# InterfacePagamentos.net
KiCad netlist of a schematic drawn in Altium Designer
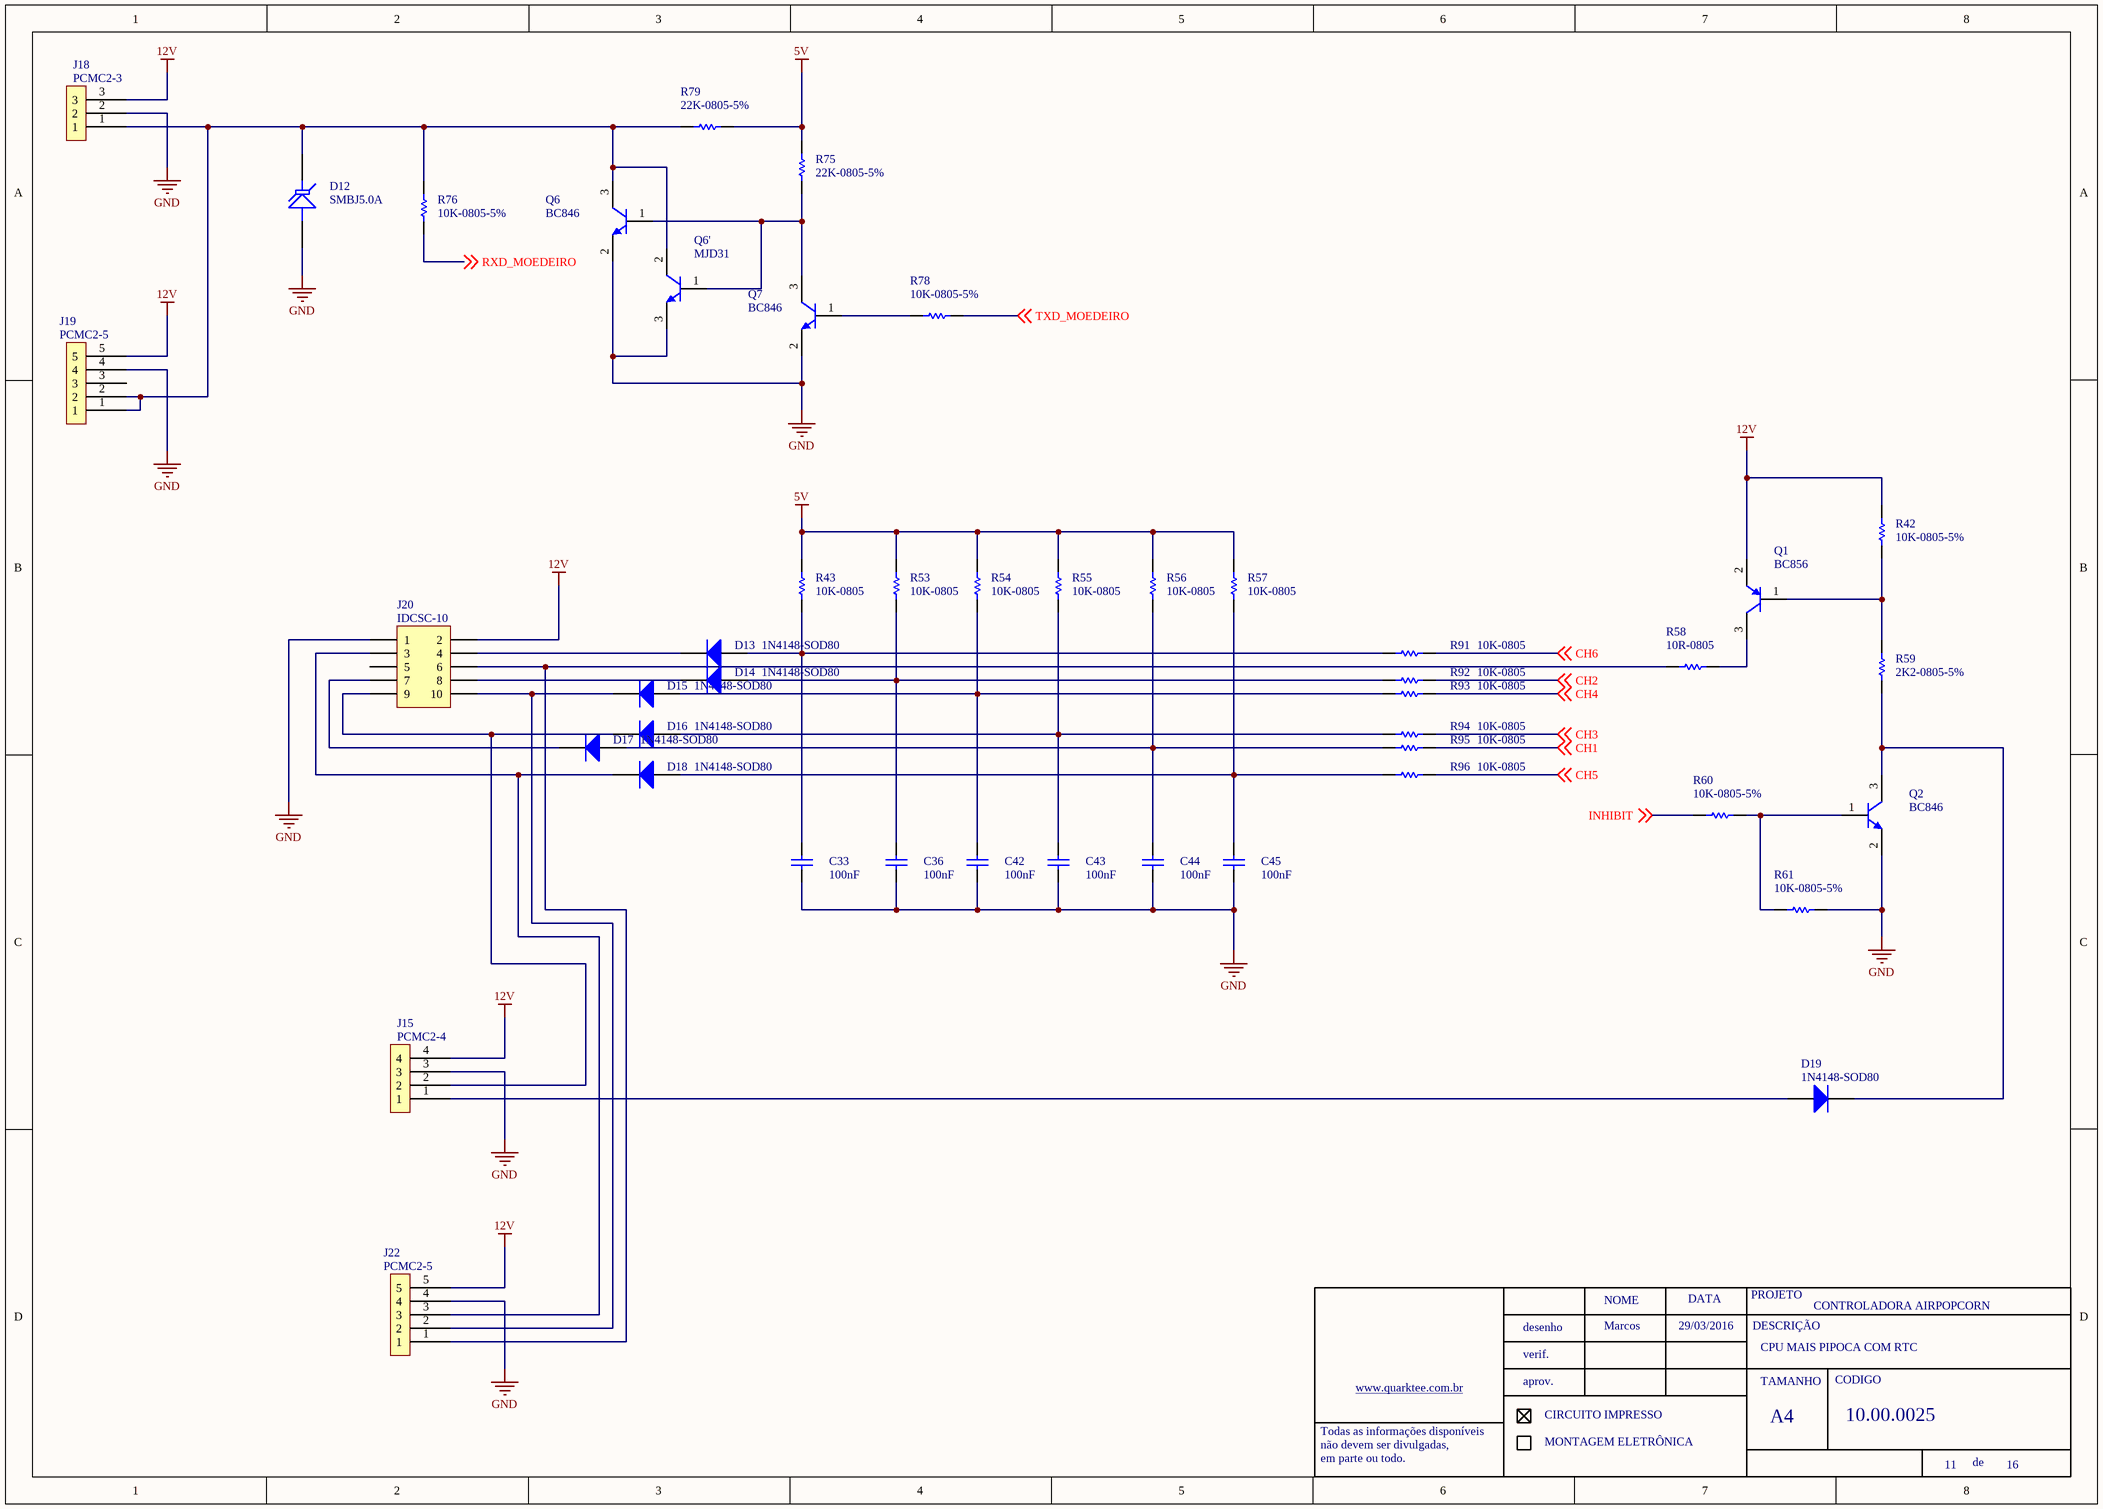
[diagram p0: InterfacePagamentos.SchDoc]

(export (version "E")
  (design (tool "Eeschema 10.0.6"))
  (components
    (comp (ref "C33")
      (value "100nF")
      (footprint "0805-REVISADO O")
      (description "100nF/50-0805-NPO")
      (libsource (lib "AquinoLib") (part "100nF/50-0805-NPO"))
    )
    (comp (ref "C36")
      (value "100nF")
      (footprint "0805-REVISADO O")
      (description "100nF/50-0805-NPO")
      (libsource (lib "AquinoLib") (part "100nF/50-0805-NPO"))
    )
    (comp (ref "C42")
      (value "100nF")
      (footprint "0805-REVISADO O")
      (description "100nF/50-0805-NPO")
      (libsource (lib "AquinoLib") (part "100nF/50-0805-NPO"))
    )
    (comp (ref "C43")
      (value "100nF")
      (footprint "0805-REVISADO O")
      (description "100nF/50-0805-NPO")
      (libsource (lib "AquinoLib") (part "100nF/50-0805-NPO"))
    )
    (comp (ref "C44")
      (value "100nF")
      (footprint "0805-REVISADO O")
      (description "100nF/50-0805-NPO")
      (libsource (lib "AquinoLib") (part "100nF/50-0805-NPO"))
    )
    (comp (ref "C45")
      (value "100nF")
      (footprint "0805-REVISADO O")
      (description "100nF/50-0805-NPO")
      (libsource (lib "AquinoLib") (part "100nF/50-0805-NPO"))
    )
    (comp (ref "D12")
      (value "SMBJ5.0A")
      (footprint "SMB/DO-214AA")
      (libsource (lib "AquinoLib") (part "SMBJ5.0A"))
    )
    (comp (ref "D13")
      (value "1N4148-SOD80")
      (footprint "MINIMLEF/SOD80")
      (libsource (lib "AquinoLib") (part "1N4148-SOD80"))
    )
    (comp (ref "D14")
      (value "1N4148-SOD80")
      (footprint "MINIMLEF/SOD80")
      (libsource (lib "AquinoLib") (part "1N4148-SOD80"))
    )
    (comp (ref "D15")
      (value "1N4148-SOD80")
      (footprint "MINIMLEF/SOD80")
      (libsource (lib "AquinoLib") (part "1N4148-SOD80"))
    )
    (comp (ref "D16")
      (value "1N4148-SOD80")
      (footprint "MINIMLEF/SOD80")
      (libsource (lib "AquinoLib") (part "1N4148-SOD80"))
    )
    (comp (ref "D17")
      (value "1N4148-SOD80")
      (footprint "MINIMLEF/SOD80")
      (libsource (lib "AquinoLib") (part "1N4148-SOD80"))
    )
    (comp (ref "D18")
      (value "1N4148-SOD80")
      (footprint "MINIMLEF/SOD80")
      (libsource (lib "AquinoLib") (part "1N4148-SOD80"))
    )
    (comp (ref "D19")
      (value "1N4148-SOD80")
      (footprint "MINIMLEF/SOD80")
      (libsource (lib "AquinoLib") (part "1N4148-SOD80"))
    )
    (comp (ref "J15") (value "PCMC2-4") (footprint "PCMC2-4") (libsource (lib "AquinoLib") (part "PCMC2-4")))
    (comp (ref "J18") (value "PCMC2-3") (footprint "PCMC2-3") (libsource (lib "AquinoLib") (part "PCMC2-3")))
    (comp (ref "J19") (value "PCMC2-5") (footprint "PCMC2-5") (libsource (lib "AquinoLib") (part "PCMC2-5")))
    (comp (ref "J20")
      (value "IDCSC-10")
      (footprint "IDCSC-10")
      (description "CONECTOR HEADER 10 VIAS 90º")
      (libsource (lib "ChaveDigital3") (part "IDCSN"))
    )
    (comp (ref "J22") (value "PCMC2-5") (footprint "PCMC2-5") (libsource (lib "AquinoLib") (part "PCMC2-5")))
    (comp (ref "Q1")
      (value "BC856")
      (footprint "SOT23 - REVISAD")
      (description "BC856L")
      (libsource (lib "AquinoLib") (part "BC856L"))
    )
    (comp (ref "Q2")
      (value "BC846")
      (footprint "SOT23 - REVISAD")
      (description "BC846L")
      (libsource (lib "AquinoLib") (part "BC846"))
    )
    (comp (ref "Q6")
      (value "BC846")
      (footprint "SOT23 - REVISAD")
      (description "BC846L")
      (libsource (lib "AquinoLib") (part "BC846"))
    )
    (comp (ref "Q6'")
      (value "MJD31")
      (footprint "DPAK REVISADO O")
      (libsource (lib "AquinoLib") (part "MJD31"))
    )
    (comp (ref "Q7")
      (value "BC846")
      (footprint "SOT23 - REVISAD")
      (description "BC846L")
      (libsource (lib "AquinoLib") (part "BC846"))
    )
    (comp (ref "R42")
      (value "10K-0805-5%")
      (footprint "0805-REVISADO O")
      (libsource (lib "AquinoLib") (part "10K-0805-5%"))
    )
    (comp (ref "R43")
      (value "10K-0805")
      (footprint "0805-REVISADO O")
      (description "4K7-1206-5%")
      (libsource (lib "AquinoLib") (part "4K7-1206-5%"))
    )
    (comp (ref "R53")
      (value "10K-0805")
      (footprint "0805-REVISADO O")
      (description "4K7-1206-5%")
      (libsource (lib "AquinoLib") (part "4K7-1206-5%"))
    )
    (comp (ref "R54")
      (value "10K-0805")
      (footprint "0805-REVISADO O")
      (description "4K7-1206-5%")
      (libsource (lib "AquinoLib") (part "4K7-1206-5%"))
    )
    (comp (ref "R55")
      (value "10K-0805")
      (footprint "0805-REVISADO O")
      (description "4K7-1206-5%")
      (libsource (lib "AquinoLib") (part "4K7-1206-5%"))
    )
    (comp (ref "R56")
      (value "10K-0805")
      (footprint "0805-REVISADO O")
      (description "4K7-1206-5%")
      (libsource (lib "AquinoLib") (part "4K7-1206-5%"))
    )
    (comp (ref "R57")
      (value "10K-0805")
      (footprint "0805-REVISADO O")
      (description "4K7-1206-5%")
      (libsource (lib "AquinoLib") (part "4K7-1206-5%"))
    )
    (comp (ref "R58")
      (value "10R-0805")
      (footprint "1206-REVISADO O")
      (description "10K-0805-5%")
      (libsource (lib "AquinoLib") (part "10K-0805-5%"))
    )
    (comp (ref "R59")
      (value "2K2-0805-5%")
      (footprint "0805-REVISADO O")
      (description "4K7-1206-5%")
      (libsource (lib "AquinoLib") (part "4K7-1206-5%"))
    )
    (comp (ref "R60")
      (value "10K-0805-5%")
      (footprint "0805-REVISADO O")
      (libsource (lib "AquinoLib") (part "10K-0805-5%"))
    )
    (comp (ref "R61")
      (value "10K-0805-5%")
      (footprint "0805-REVISADO O")
      (libsource (lib "AquinoLib") (part "10K-0805-5%"))
    )
    (comp (ref "R75")
      (value "22K-0805-5%")
      (footprint "0805-REVISADO O")
      (libsource (lib "AquinoLib") (part "22K-0805-5%"))
    )
    (comp (ref "R76")
      (value "10K-0805-5%")
      (footprint "0805-REVISADO O")
      (description "56K-0805-5%")
      (libsource (lib "AquinoLib") (part "56K-0805-5%"))
    )
    (comp (ref "R78")
      (value "10K-0805-5%")
      (footprint "0805-REVISADO O")
      (libsource (lib "AquinoLib") (part "10K-0805-5%"))
    )
    (comp (ref "R79")
      (value "22K-0805-5%")
      (footprint "0805-REVISADO O")
      (libsource (lib "AquinoLib") (part "22K-0805-5%"))
    )
    (comp (ref "R91")
      (value "10K-0805")
      (footprint "0805-REVISADO O")
      (description "4K7-1206-5%")
      (libsource (lib "AquinoLib") (part "4K7-1206-5%"))
    )
    (comp (ref "R92")
      (value "10K-0805")
      (footprint "0805-REVISADO O")
      (description "4K7-1206-5%")
      (libsource (lib "AquinoLib") (part "4K7-1206-5%"))
    )
    (comp (ref "R93")
      (value "10K-0805")
      (footprint "0805-REVISADO O")
      (description "4K7-1206-5%")
      (libsource (lib "AquinoLib") (part "4K7-1206-5%"))
    )
    (comp (ref "R94")
      (value "10K-0805")
      (footprint "0805-REVISADO O")
      (description "4K7-1206-5%")
      (libsource (lib "AquinoLib") (part "4K7-1206-5%"))
    )
    (comp (ref "R95")
      (value "10K-0805")
      (footprint "0805-REVISADO O")
      (description "4K7-1206-5%")
      (libsource (lib "AquinoLib") (part "4K7-1206-5%"))
    )
    (comp (ref "R96")
      (value "10K-0805")
      (footprint "0805-REVISADO O")
      (description "4K7-1206-5%")
      (libsource (lib "AquinoLib") (part "4K7-1206-5%"))
    )
  )
  (nets
    (net (code "1") (name "5V") (class "Default")
      (node (ref "R43") (pin "2") (pinfunction "2_2") (pintype "passive"))
      (node (ref "R53") (pin "2") (pinfunction "2_2") (pintype "passive"))
      (node (ref "R54") (pin "2") (pinfunction "2_2") (pintype "passive"))
      (node (ref "R55") (pin "2") (pinfunction "2_2") (pintype "passive"))
      (node (ref "R56") (pin "2") (pinfunction "2_2") (pintype "passive"))
      (node (ref "R57") (pin "2") (pinfunction "2_2") (pintype "passive"))
      (node (ref "R75") (pin "2") (pinfunction "2_2") (pintype "passive"))
      (node (ref "R79") (pin "2") (pinfunction "2_2") (pintype "passive"))
    )
    (net (code "2") (name "12V") (class "Default")
      (node (ref "J15") (pin "4") (pinfunction "4_4") (pintype "passive"))
      (node (ref "J18") (pin "3") (pinfunction "3_3") (pintype "passive"))
      (node (ref "J19") (pin "5") (pinfunction "5_5") (pintype "passive"))
      (node (ref "J20") (pin "2") (pinfunction "2_2") (pintype "passive"))
      (node (ref "J22") (pin "5") (pinfunction "5_5") (pintype "passive"))
      (node (ref "Q1") (pin "2") (pinfunction "E_2") (pintype "passive"))
      (node (ref "R42") (pin "2") (pinfunction "2_2") (pintype "passive"))
    )
    (net (code "3") (name "CH1") (class "Default")
      (node (ref "R95") (pin "1") (pinfunction "1_1") (pintype "passive"))
    )
    (net (code "4") (name "CH2") (class "Default")
      (node (ref "R92") (pin "1") (pinfunction "1_1") (pintype "passive"))
    )
    (net (code "5") (name "CH3") (class "Default")
      (node (ref "R94") (pin "1") (pinfunction "1_1") (pintype "passive"))
    )
    (net (code "6") (name "CH4") (class "Default")
      (node (ref "R93") (pin "1") (pinfunction "1_1") (pintype "passive"))
    )
    (net (code "7") (name "CH5") (class "Default")
      (node (ref "R96") (pin "1") (pinfunction "1_1") (pintype "passive"))
    )
    (net (code "8") (name "CH6") (class "Default")
      (node (ref "R91") (pin "1") (pinfunction "1_1") (pintype "passive"))
    )
    (net (code "9") (name "GND") (class "Default")
      (node (ref "C33") (pin "1") (pinfunction "1_1") (pintype "passive"))
      (node (ref "C36") (pin "1") (pinfunction "1_1") (pintype "passive"))
      (node (ref "C42") (pin "1") (pinfunction "1_1") (pintype "passive"))
      (node (ref "C43") (pin "1") (pinfunction "1_1") (pintype "passive"))
      (node (ref "C44") (pin "1") (pinfunction "1_1") (pintype "passive"))
      (node (ref "C45") (pin "1") (pinfunction "1_1") (pintype "passive"))
      (node (ref "D12") (pin "1") (pinfunction "A_1") (pintype "passive"))
      (node (ref "J15") (pin "3") (pinfunction "3_3") (pintype "passive"))
      (node (ref "J18") (pin "2") (pinfunction "2_2") (pintype "passive"))
      (node (ref "J19") (pin "4") (pinfunction "4_4") (pintype "passive"))
      (node (ref "J20") (pin "1") (pinfunction "1_1") (pintype "passive"))
      (node (ref "J22") (pin "4") (pinfunction "4_4") (pintype "passive"))
      (node (ref "Q2") (pin "2") (pinfunction "E_2") (pintype "passive"))
      (node (ref "Q6") (pin "2") (pinfunction "E_2") (pintype "passive"))
      (node (ref "Q6'") (pin "3") (pinfunction "E_3") (pintype "passive"))
      (node (ref "Q7") (pin "2") (pinfunction "E_2") (pintype "passive"))
      (node (ref "R61") (pin "2") (pinfunction "2_2") (pintype "passive"))
    )
    (net (code "10") (name "INHIBIT") (class "Default")
      (node (ref "R60") (pin "1") (pinfunction "1_1") (pintype "passive"))
    )
    (net (code "11") (name "Net-(C33-Pad2)") (class "Default")
      (node (ref "C33") (pin "2") (pinfunction "2_2") (pintype "passive"))
      (node (ref "D13") (pin "1") (pinfunction "1_1") (pintype "passive"))
      (node (ref "R43") (pin "1") (pinfunction "1_1") (pintype "passive"))
      (node (ref "R91") (pin "2") (pinfunction "2_2") (pintype "passive"))
    )
    (net (code "12") (name "Net-(C36-Pad2)") (class "Default")
      (node (ref "C36") (pin "2") (pinfunction "2_2") (pintype "passive"))
      (node (ref "D14") (pin "1") (pinfunction "1_1") (pintype "passive"))
      (node (ref "R53") (pin "1") (pinfunction "1_1") (pintype "passive"))
      (node (ref "R92") (pin "2") (pinfunction "2_2") (pintype "passive"))
    )
    (net (code "13") (name "Net-(C42-Pad2)") (class "Default")
      (node (ref "C42") (pin "2") (pinfunction "2_2") (pintype "passive"))
      (node (ref "D15") (pin "1") (pinfunction "1_1") (pintype "passive"))
      (node (ref "R54") (pin "1") (pinfunction "1_1") (pintype "passive"))
      (node (ref "R93") (pin "2") (pinfunction "2_2") (pintype "passive"))
    )
    (net (code "14") (name "Net-(C43-Pad2)") (class "Default")
      (node (ref "C43") (pin "2") (pinfunction "2_2") (pintype "passive"))
      (node (ref "D16") (pin "1") (pinfunction "1_1") (pintype "passive"))
      (node (ref "R55") (pin "1") (pinfunction "1_1") (pintype "passive"))
      (node (ref "R94") (pin "2") (pinfunction "2_2") (pintype "passive"))
    )
    (net (code "15") (name "Net-(C44-Pad2)") (class "Default")
      (node (ref "C44") (pin "2") (pinfunction "2_2") (pintype "passive"))
      (node (ref "D17") (pin "1") (pinfunction "1_1") (pintype "passive"))
      (node (ref "R56") (pin "1") (pinfunction "1_1") (pintype "passive"))
      (node (ref "R95") (pin "2") (pinfunction "2_2") (pintype "passive"))
    )
    (net (code "16") (name "Net-(C45-Pad2)") (class "Default")
      (node (ref "C45") (pin "2") (pinfunction "2_2") (pintype "passive"))
      (node (ref "D18") (pin "1") (pinfunction "1_1") (pintype "passive"))
      (node (ref "R57") (pin "1") (pinfunction "1_1") (pintype "passive"))
      (node (ref "R96") (pin "2") (pinfunction "2_2") (pintype "passive"))
    )
    (net (code "17") (name "Net-(D12-K)") (class "Default")
      (node (ref "D12") (pin "2") (pinfunction "K_2") (pintype "passive"))
      (node (ref "J18") (pin "1") (pinfunction "1_1") (pintype "passive"))
      (node (ref "J19") (pin "1") (pinfunction "1_1") (pintype "passive"))
      (node (ref "J19") (pin "2") (pinfunction "2_2") (pintype "passive"))
      (node (ref "Q6") (pin "3") (pinfunction "C_3") (pintype "passive"))
      (node (ref "Q6'") (pin "2") (pinfunction "C_2") (pintype "passive"))
      (node (ref "R76") (pin "1") (pinfunction "1_1") (pintype "passive"))
      (node (ref "R79") (pin "1") (pinfunction "1_1") (pintype "passive"))
    )
    (net (code "18") (name "Net-(D13-Pad2)") (class "Default")
      (node (ref "D13") (pin "2") (pinfunction "2_2") (pintype "passive"))
      (node (ref "J20") (pin "4") (pinfunction "4_4") (pintype "passive"))
    )
    (net (code "19") (name "Net-(D14-Pad2)") (class "Default")
      (node (ref "D14") (pin "2") (pinfunction "2_2") (pintype "passive"))
      (node (ref "J20") (pin "8") (pinfunction "8_8") (pintype "passive"))
    )
    (net (code "20") (name "Net-(D15-Pad2)") (class "Default")
      (node (ref "D15") (pin "2") (pinfunction "2_2") (pintype "passive"))
      (node (ref "J20") (pin "10") (pinfunction "10_10") (pintype "passive"))
      (node (ref "J22") (pin "2") (pinfunction "2_2") (pintype "passive"))
    )
    (net (code "21") (name "Net-(D16-Pad2)") (class "Default")
      (node (ref "D16") (pin "2") (pinfunction "2_2") (pintype "passive"))
      (node (ref "J15") (pin "2") (pinfunction "2_2") (pintype "passive"))
      (node (ref "J20") (pin "9") (pinfunction "9_9") (pintype "passive"))
    )
    (net (code "22") (name "Net-(D17-Pad2)") (class "Default")
      (node (ref "D17") (pin "2") (pinfunction "2_2") (pintype "passive"))
      (node (ref "J20") (pin "7") (pinfunction "7_7") (pintype "passive"))
    )
    (net (code "23") (name "Net-(D18-Pad2)") (class "Default")
      (node (ref "D18") (pin "2") (pinfunction "2_2") (pintype "passive"))
      (node (ref "J20") (pin "3") (pinfunction "3_3") (pintype "passive"))
      (node (ref "J22") (pin "3") (pinfunction "3_3") (pintype "passive"))
    )
    (net (code "24") (name "Net-(D19-Pad1)") (class "Default")
      (node (ref "D19") (pin "1") (pinfunction "1_1") (pintype "passive"))
      (node (ref "J15") (pin "1") (pinfunction "1_1") (pintype "passive"))
    )
    (net (code "25") (name "Net-(J20-Pad6)") (class "Default")
      (node (ref "J20") (pin "6") (pinfunction "6_6") (pintype "passive"))
      (node (ref "J22") (pin "1") (pinfunction "1_1") (pintype "passive"))
      (node (ref "R58") (pin "2") (pinfunction "2_2") (pintype "passive"))
    )
    (net (code "26") (name "Net-(Q1-B)") (class "Default")
      (node (ref "Q1") (pin "1") (pinfunction "B_1") (pintype "passive"))
      (node (ref "R42") (pin "1") (pinfunction "1_1") (pintype "passive"))
      (node (ref "R59") (pin "2") (pinfunction "2_2") (pintype "passive"))
    )
    (net (code "27") (name "Net-(Q1-C)") (class "Default")
      (node (ref "Q1") (pin "3") (pinfunction "C_3") (pintype "passive"))
      (node (ref "R58") (pin "1") (pinfunction "1_1") (pintype "passive"))
    )
    (net (code "28") (name "Net-(Q2-B)") (class "Default")
      (node (ref "Q2") (pin "1") (pinfunction "B_1") (pintype "passive"))
      (node (ref "R60") (pin "2") (pinfunction "2_2") (pintype "passive"))
      (node (ref "R61") (pin "1") (pinfunction "1_1") (pintype "passive"))
    )
    (net (code "29") (name "Net-(Q2-C)") (class "Default")
      (node (ref "D19") (pin "2") (pinfunction "2_2") (pintype "passive"))
      (node (ref "Q2") (pin "3") (pinfunction "C_3") (pintype "passive"))
      (node (ref "R59") (pin "1") (pinfunction "1_1") (pintype "passive"))
    )
    (net (code "30") (name "Net-(Q6'-B)") (class "Default")
      (node (ref "Q6") (pin "1") (pinfunction "B_1") (pintype "passive"))
      (node (ref "Q6'") (pin "1") (pinfunction "B_1") (pintype "passive"))
      (node (ref "Q7") (pin "3") (pinfunction "C_3") (pintype "passive"))
      (node (ref "R75") (pin "1") (pinfunction "1_1") (pintype "passive"))
    )
    (net (code "31") (name "Net-(Q7-B)") (class "Default")
      (node (ref "Q7") (pin "1") (pinfunction "B_1") (pintype "passive"))
      (node (ref "R78") (pin "1") (pinfunction "1_1") (pintype "passive"))
    )
    (net (code "32") (name "RXD_MOEDEIRO") (class "Default")
      (node (ref "R76") (pin "2") (pinfunction "2_2") (pintype "passive"))
    )
    (net (code "33") (name "TXD_MOEDEIRO") (class "Default")
      (node (ref "R78") (pin "2") (pinfunction "2_2") (pintype "passive"))
    )
    (net (code "34") (name "unconnected-(J19-Pad3)") (class "Default")
      (node (ref "J19") (pin "3") (pinfunction "3_3") (pintype "passive"))
    )
    (net (code "35") (name "unconnected-(J20-Pad5)") (class "Default")
      (node (ref "J20") (pin "5") (pinfunction "5_5") (pintype "passive"))
    )
  )
)
